# 8pos_switch.net
KiCad netlist of a schematic drawn in Altium Designer
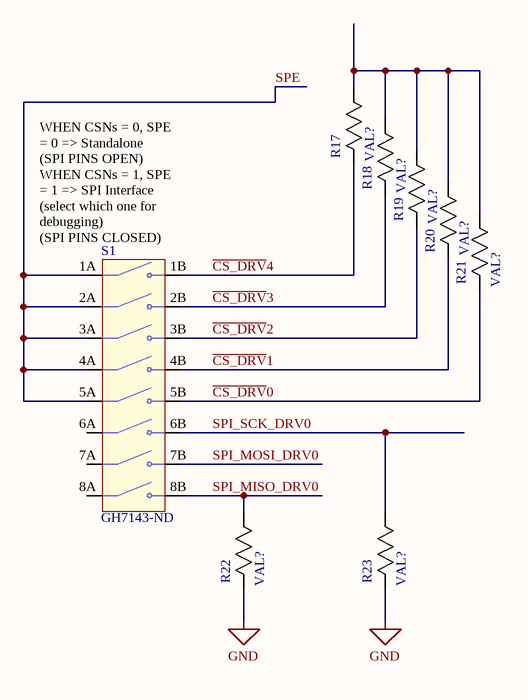
[diagram p0: 8pos_switch.SchDoc]

(export (version "E")
  (design (tool "Eeschema 10.0.6"))
  (components
    (comp (ref "R17")
      (value "VAL?")
      (footprint "0805")
      (description "Default Resistor Symbol")
      (fields (field (name "TOLERANCE") "5%") (field (name "PART NUMBER") "RES 10k 1/8W - 5%"))
      (libsource (lib "Resistor_Library") (part "RES_DEFAULT"))
    )
    (comp (ref "R18")
      (value "VAL?")
      (footprint "0805")
      (description "Default Resistor Symbol")
      (fields (field (name "TOLERANCE") "5%") (field (name "PART NUMBER") "RES 10k 1/8W - 5%"))
      (libsource (lib "Resistor_Library") (part "RES_DEFAULT"))
    )
    (comp (ref "R19")
      (value "VAL?")
      (footprint "0805")
      (description "Default Resistor Symbol")
      (fields (field (name "TOLERANCE") "5%") (field (name "PART NUMBER") "RES 10k 1/8W - 5%"))
      (libsource (lib "Resistor_Library") (part "RES_DEFAULT"))
    )
    (comp (ref "R20")
      (value "VAL?")
      (footprint "0805")
      (description "Default Resistor Symbol")
      (fields (field (name "TOLERANCE") "5%") (field (name "PART NUMBER") "RES 10k 1/8W - 5%"))
      (libsource (lib "Resistor_Library") (part "RES_DEFAULT"))
    )
    (comp (ref "R21")
      (value "VAL?")
      (footprint "0805")
      (description "Default Resistor Symbol")
      (fields (field (name "TOLERANCE") "5%") (field (name "PART NUMBER") "RES 10k 1/8W - 5%"))
      (libsource (lib "Resistor_Library") (part "RES_DEFAULT"))
    )
    (comp (ref "R22")
      (value "VAL?")
      (footprint "0805")
      (description "Default Resistor Symbol")
      (fields (field (name "TOLERANCE") "5%") (field (name "PART NUMBER") "RES 10k 1/8W - 5%"))
      (libsource (lib "Resistor_Library") (part "RES_DEFAULT"))
    )
    (comp (ref "R23")
      (value "VAL?")
      (footprint "0805")
      (description "Default Resistor Symbol")
      (fields (field (name "TOLERANCE") "5%") (field (name "PART NUMBER") "RES 10k 1/8W - 5%"))
      (libsource (lib "Resistor_Library") (part "RES_DEFAULT"))
    )
    (comp (ref "S1")
      (value "SW 8POS PIANO DIP")
      (footprint "SW 8POS PIANO")
      (fields
        (field (name "MANUFACTURER PART NUMBER") "76PSB08ST\r\nTL3305BF260QG")
        (field (name "SUPPLIER PART NUMBER 1") "GH7143-ND")
      )
      (libsource (lib "Switch_Library") (part "SW 8POS PIANO DIP"))
    )
  )
  (nets
    (net (code "1") (name "/SPE") (class "Default")
      (node (ref "S1") (pin "1A") (pinfunction "COM1_1A") (pintype "passive"))
      (node (ref "S1") (pin "2A") (pinfunction "COM2_2A") (pintype "passive"))
      (node (ref "S1") (pin "3A") (pinfunction "COM3_3A") (pintype "passive"))
      (node (ref "S1") (pin "4A") (pinfunction "COM4_4A") (pintype "passive"))
      (node (ref "S1") (pin "5A") (pinfunction "COM5_5A") (pintype "passive"))
    )
    (net (code "2") (name "/SPI_MISO_DRV0") (class "Default")
      (node (ref "R22") (pin "1") (pinfunction "R1_1") (pintype "passive"))
      (node (ref "S1") (pin "8B") (pinfunction "NO8_8B") (pintype "passive"))
    )
    (net (code "3") (name "/SPI_MOSI_DRV0") (class "Default")
      (node (ref "S1") (pin "7B") (pinfunction "NO7_7B") (pintype "passive"))
    )
    (net (code "4") (name "/SPI_SCK_DRV0") (class "Default")
      (node (ref "R23") (pin "1") (pinfunction "R1_1") (pintype "passive"))
      (node (ref "S1") (pin "6B") (pinfunction "NO6_6B") (pintype "passive"))
    )
    (net (code "5") (name "/~{CS_DRV}0") (class "Default")
      (node (ref "R21") (pin "2") (pinfunction "R2_2") (pintype "passive"))
      (node (ref "S1") (pin "5B") (pinfunction "NO5_5B") (pintype "passive"))
    )
    (net (code "6") (name "/~{CS_DRV}1") (class "Default")
      (node (ref "R20") (pin "2") (pinfunction "R2_2") (pintype "passive"))
      (node (ref "S1") (pin "4B") (pinfunction "NO4_4B") (pintype "passive"))
    )
    (net (code "7") (name "/~{CS_DRV}2") (class "Default")
      (node (ref "R19") (pin "2") (pinfunction "R2_2") (pintype "passive"))
      (node (ref "S1") (pin "3B") (pinfunction "NO3_3B") (pintype "passive"))
    )
    (net (code "8") (name "/~{CS_DRV}3") (class "Default")
      (node (ref "R18") (pin "2") (pinfunction "R2_2") (pintype "passive"))
      (node (ref "S1") (pin "2B") (pinfunction "NO2_2B") (pintype "passive"))
    )
    (net (code "9") (name "/~{CS_DRV}4") (class "Default")
      (node (ref "R17") (pin "2") (pinfunction "R2_2") (pintype "passive"))
      (node (ref "S1") (pin "1B") (pinfunction "NO1_1B") (pintype "passive"))
    )
    (net (code "10") (name "GND") (class "Default")
      (node (ref "R22") (pin "2") (pinfunction "R2_2") (pintype "passive"))
      (node (ref "R23") (pin "2") (pinfunction "R2_2") (pintype "passive"))
    )
    (net (code "11") (name "Net-(R17-R1)") (class "Default")
      (node (ref "R17") (pin "1") (pinfunction "R1_1") (pintype "passive"))
      (node (ref "R18") (pin "1") (pinfunction "R1_1") (pintype "passive"))
      (node (ref "R19") (pin "1") (pinfunction "R1_1") (pintype "passive"))
      (node (ref "R20") (pin "1") (pinfunction "R1_1") (pintype "passive"))
      (node (ref "R21") (pin "1") (pinfunction "R1_1") (pintype "passive"))
    )
    (net (code "12") (name "unconnected-(S1-COM6-Pad6A)") (class "Default")
      (node (ref "S1") (pin "6A") (pinfunction "COM6_6A") (pintype "passive"))
    )
    (net (code "13") (name "unconnected-(S1-COM7-Pad7A)") (class "Default")
      (node (ref "S1") (pin "7A") (pinfunction "COM7_7A") (pintype "passive"))
    )
    (net (code "14") (name "unconnected-(S1-COM8-Pad8A)") (class "Default")
      (node (ref "S1") (pin "8A") (pinfunction "COM8_8A") (pintype "passive"))
    )
  )
)
